# SCH_Roboliga2026_TOP_2026-04-12.net
KiCad netlist of a schematic drawn in EasyEDA
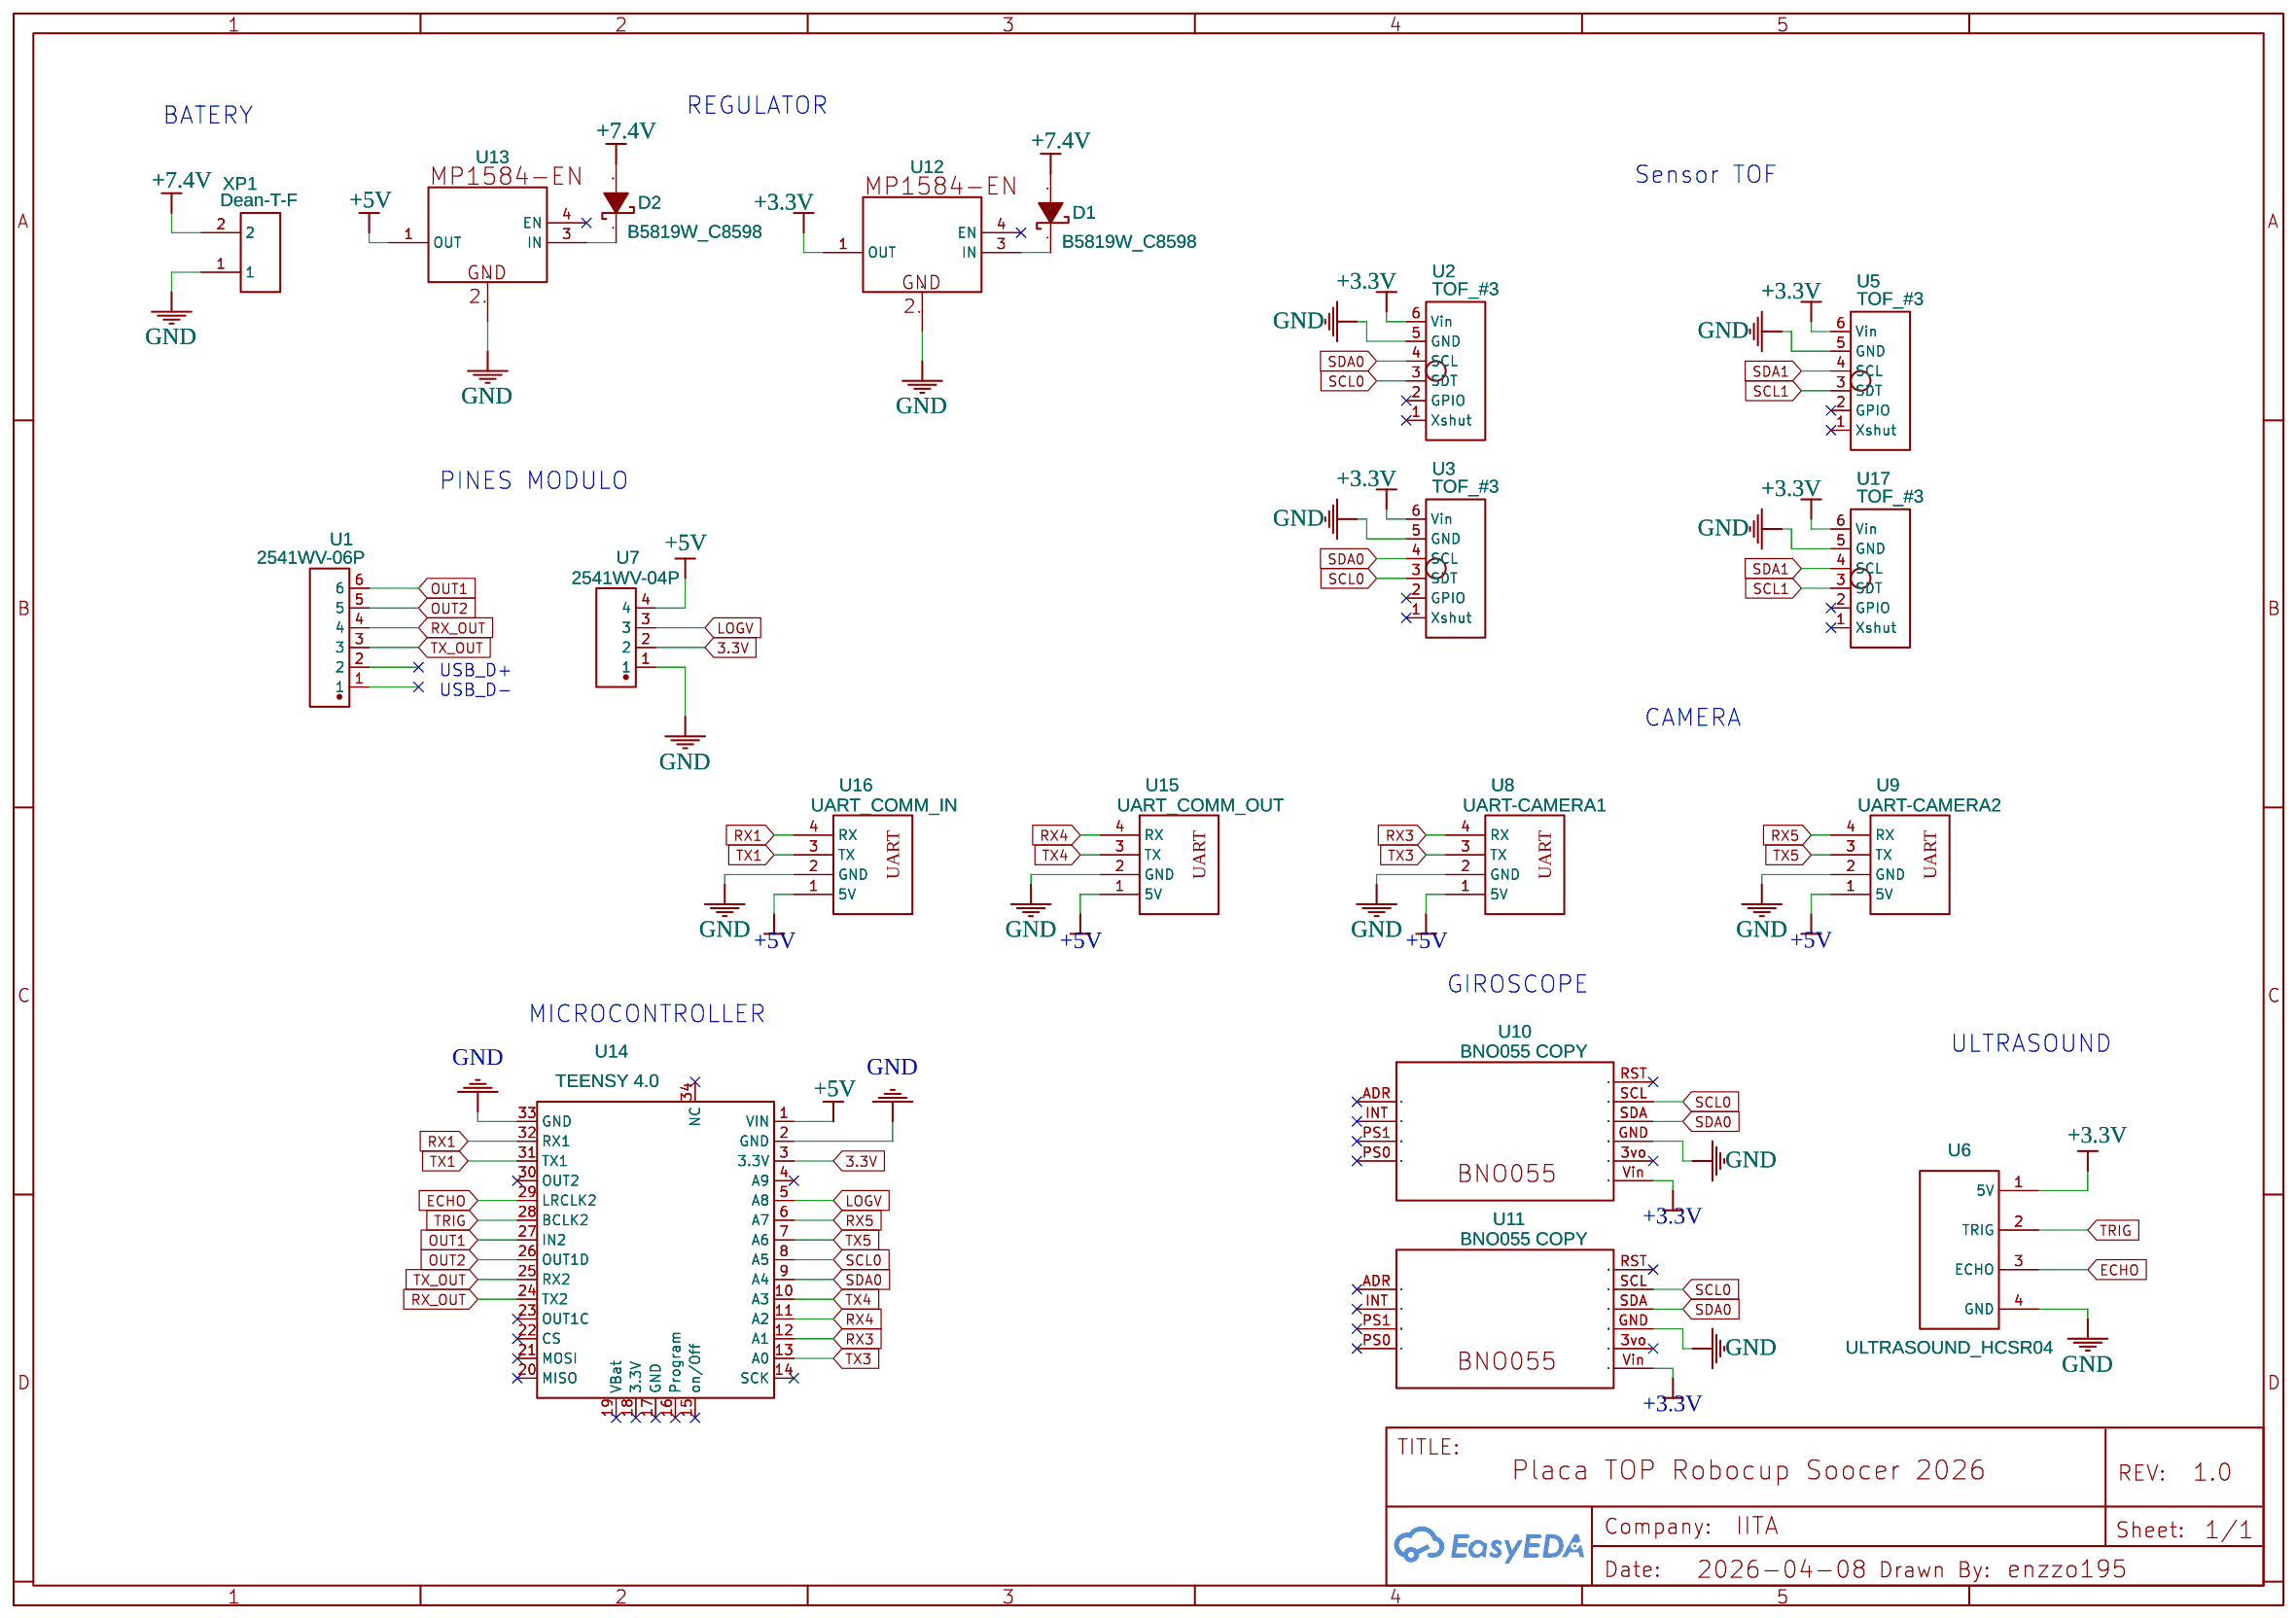
[diagram p0: schematic sheet]

(export (version "E")
  (design (tool "Eeschema 10.0.6"))
  (components
    (comp (ref "D1")
      (value "B5819W_C8598")
      (fields (field (name "Manufacturer Part") "B5819W SL") (field (name "Manufacturer") "CJ(江苏长电/长晶)"))
      (libsource (lib "") (part "B5819W_C8598"))
    )
    (comp (ref "D2")
      (value "B5819W_C8598")
      (fields (field (name "Manufacturer Part") "B5819W SL") (field (name "Manufacturer") "CJ(江苏长电/长晶)"))
      (libsource (lib "") (part "B5819W_C8598"))
    )
    (comp (ref "U1")
      (value "2541WV-06P")
      (fields (field (name "Manufacturer") "HanElectricity(瀚源)"))
      (libsource (lib "") (part "2541WV-06P"))
    )
    (comp (ref "U2") (value "TOF_#3") (libsource (lib "") (part "TOF_#3")))
    (comp (ref "U3") (value "TOF_#3") (libsource (lib "") (part "TOF_#3")))
    (comp (ref "U5") (value "TOF_#3") (libsource (lib "") (part "TOF_#3")))
    (comp (ref "U6") (value "ULTRASOUND_HCSR04") (libsource (lib "") (part "SIMBOLO_HCSR04")))
    (comp (ref "U7")
      (value "2541WV-04P")
      (fields (field (name "Manufacturer") "HanElectricity(瀚源)"))
      (libsource (lib "") (part "2541WV-04P"))
    )
    (comp (ref "U8")
      (value "UART-CAMERA1")
      (fields (field (name "Manufacturer Part") "UART"))
      (libsource (lib "") (part "UART"))
    )
    (comp (ref "U9")
      (value "UART-CAMERA2")
      (fields (field (name "Manufacturer Part") "UART"))
      (libsource (lib "") (part "UART"))
    )
    (comp (ref "U10") (value "BNO055 COPY") (libsource (lib "") (part "BNO055 COPY")))
    (comp (ref "U11") (value "BNO055 COPY") (libsource (lib "") (part "BNO055 COPY")))
    (comp (ref "U12")
      (value "MP1584EN 4-Pin SIP Module")
      (libsource (lib "") (part "MP1584EN 4-Pin SIP Module"))
    )
    (comp (ref "U13")
      (value "MP1584EN 4-Pin SIP Module")
      (libsource (lib "") (part "MP1584EN 4-Pin SIP Module"))
    )
    (comp (ref "U14")
      (value "TEENSY 4.0")
      (fields (field (name "Manufacturer Part") "Teensy 4.0"))
      (libsource (lib "") (part "TEENSY 4.0"))
    )
    (comp (ref "U15")
      (value "UART_COMM_OUT")
      (fields (field (name "Manufacturer Part") "UART"))
      (libsource (lib "") (part "UART"))
    )
    (comp (ref "U16")
      (value "UART_COMM_IN")
      (fields (field (name "Manufacturer Part") "UART"))
      (libsource (lib "") (part "UART"))
    )
    (comp (ref "U17") (value "TOF_#3") (libsource (lib "") (part "TOF_#3")))
    (comp (ref "XP1") (value "Dean-T-F") (libsource (lib "") (part "Dean-T-F")))
  )
  (nets
    (net (code "1") (name "+3.3V") (class "Default")
      (node (ref "U10") (pin "Vin") (pinfunction "Vin_Vin") (pintype "unspecified"))
      (node (ref "U11") (pin "Vin") (pinfunction "Vin_Vin") (pintype "unspecified"))
      (node (ref "U12") (pin "1") (pinfunction "OUT_1") (pintype "unspecified"))
      (node (ref "U17") (pin "6") (pinfunction "Vin_6") (pintype "unspecified"))
      (node (ref "U2") (pin "6") (pinfunction "Vin_6") (pintype "unspecified"))
      (node (ref "U3") (pin "6") (pinfunction "Vin_6") (pintype "unspecified"))
      (node (ref "U5") (pin "6") (pinfunction "Vin_6") (pintype "unspecified"))
      (node (ref "U6") (pin "1") (pinfunction "5V_1") (pintype "unspecified"))
    )
    (net (code "2") (name "+5V") (class "Default")
      (node (ref "U13") (pin "1") (pinfunction "OUT_1") (pintype "unspecified"))
      (node (ref "U14") (pin "1") (pinfunction "VIN_1") (pintype "unspecified"))
      (node (ref "U15") (pin "1") (pinfunction "5V_1") (pintype "unspecified"))
      (node (ref "U16") (pin "1") (pinfunction "5V_1") (pintype "unspecified"))
      (node (ref "U7") (pin "4") (pinfunction "4_4") (pintype "unspecified"))
      (node (ref "U8") (pin "1") (pinfunction "5V_1") (pintype "unspecified"))
      (node (ref "U9") (pin "1") (pinfunction "5V_1") (pintype "unspecified"))
    )
    (net (code "3") (name "+7.4V") (class "Default")
      (node (ref "D1") (pin "2") (pinfunction "+_2") (pintype "unspecified"))
      (node (ref "D2") (pin "2") (pinfunction "+_2") (pintype "unspecified"))
      (node (ref "XP1") (pin "2") (pinfunction "2_2") (pintype "unspecified"))
    )
    (net (code "4") (name "3.3V") (class "Default")
      (node (ref "U14") (pin "3") (pinfunction "3.3V_3") (pintype "unspecified"))
      (node (ref "U7") (pin "2") (pinfunction "2_2") (pintype "unspecified"))
    )
    (net (code "5") (name "ECHO") (class "Default")
      (node (ref "U14") (pin "29") (pinfunction "LRCLK2_29") (pintype "unspecified"))
      (node (ref "U6") (pin "3") (pinfunction "ECHO_3") (pintype "unspecified"))
    )
    (net (code "6") (name "GND") (class "Default")
      (node (ref "U10") (pin "GND") (pinfunction "GND_GND") (pintype "unspecified"))
      (node (ref "U11") (pin "GND") (pinfunction "GND_GND") (pintype "unspecified"))
      (node (ref "U12") (pin "2") (pinfunction "GND_2") (pintype "unspecified"))
      (node (ref "U13") (pin "2") (pinfunction "GND_2") (pintype "unspecified"))
      (node (ref "U14") (pin "2") (pinfunction "GND_2") (pintype "unspecified"))
      (node (ref "U14") (pin "33") (pinfunction "GND_33") (pintype "unspecified"))
      (node (ref "U15") (pin "2") (pinfunction "GND_2") (pintype "unspecified"))
      (node (ref "U16") (pin "2") (pinfunction "GND_2") (pintype "unspecified"))
      (node (ref "U17") (pin "5") (pinfunction "GND_5") (pintype "unspecified"))
      (node (ref "U2") (pin "5") (pinfunction "GND_5") (pintype "unspecified"))
      (node (ref "U3") (pin "5") (pinfunction "GND_5") (pintype "unspecified"))
      (node (ref "U5") (pin "5") (pinfunction "GND_5") (pintype "unspecified"))
      (node (ref "U6") (pin "4") (pinfunction "GND_4") (pintype "unspecified"))
      (node (ref "U7") (pin "1") (pinfunction "1_1") (pintype "unspecified"))
      (node (ref "U8") (pin "2") (pinfunction "GND_2") (pintype "unspecified"))
      (node (ref "U9") (pin "2") (pinfunction "GND_2") (pintype "unspecified"))
      (node (ref "XP1") (pin "1") (pinfunction "1_1") (pintype "unspecified"))
    )
    (net (code "7") (name "LOGV") (class "Default")
      (node (ref "U14") (pin "5") (pinfunction "A8_5") (pintype "unspecified"))
      (node (ref "U7") (pin "3") (pinfunction "3_3") (pintype "unspecified"))
    )
    (net (code "8") (name "Net-(D1--)") (class "Default")
      (node (ref "D1") (pin "1") (pinfunction "-_1") (pintype "unspecified"))
      (node (ref "U12") (pin "3") (pinfunction "IN_3") (pintype "unspecified"))
    )
    (net (code "9") (name "Net-(D2--)") (class "Default")
      (node (ref "D2") (pin "1") (pinfunction "-_1") (pintype "unspecified"))
      (node (ref "U13") (pin "3") (pinfunction "IN_3") (pintype "unspecified"))
    )
    (net (code "10") (name "OUT1") (class "Default")
      (node (ref "U1") (pin "6") (pinfunction "6_6") (pintype "unspecified"))
      (node (ref "U14") (pin "27") (pinfunction "IN2_27") (pintype "unspecified"))
    )
    (net (code "11") (name "OUT2") (class "Default")
      (node (ref "U1") (pin "5") (pinfunction "5_5") (pintype "unspecified"))
      (node (ref "U14") (pin "26") (pinfunction "OUT1D_26") (pintype "unspecified"))
    )
    (net (code "12") (name "RX1") (class "Default")
      (node (ref "U14") (pin "32") (pinfunction "RX1_32") (pintype "unspecified"))
      (node (ref "U16") (pin "4") (pinfunction "RX_4") (pintype "unspecified"))
    )
    (net (code "13") (name "RX3") (class "Default")
      (node (ref "U14") (pin "12") (pinfunction "A1_12") (pintype "unspecified"))
      (node (ref "U8") (pin "4") (pinfunction "RX_4") (pintype "unspecified"))
    )
    (net (code "14") (name "RX4") (class "Default")
      (node (ref "U14") (pin "11") (pinfunction "A2_11") (pintype "unspecified"))
      (node (ref "U15") (pin "4") (pinfunction "RX_4") (pintype "unspecified"))
    )
    (net (code "15") (name "RX5") (class "Default")
      (node (ref "U14") (pin "6") (pinfunction "A7_6") (pintype "unspecified"))
      (node (ref "U9") (pin "4") (pinfunction "RX_4") (pintype "unspecified"))
    )
    (net (code "16") (name "RX_OUT") (class "Default")
      (node (ref "U1") (pin "4") (pinfunction "4_4") (pintype "unspecified"))
      (node (ref "U14") (pin "24") (pinfunction "TX2_24") (pintype "unspecified"))
    )
    (net (code "17") (name "SCL0") (class "Default")
      (node (ref "U10") (pin "SCL") (pinfunction "SCL_SCL") (pintype "unspecified"))
      (node (ref "U11") (pin "SCL") (pinfunction "SCL_SCL") (pintype "unspecified"))
      (node (ref "U14") (pin "8") (pinfunction "A5_8") (pintype "unspecified"))
      (node (ref "U2") (pin "3") (pinfunction "SDT_3") (pintype "unspecified"))
      (node (ref "U3") (pin "3") (pinfunction "SDT_3") (pintype "unspecified"))
    )
    (net (code "18") (name "SCL1") (class "Default")
      (node (ref "U17") (pin "3") (pinfunction "SDT_3") (pintype "unspecified"))
      (node (ref "U5") (pin "3") (pinfunction "SDT_3") (pintype "unspecified"))
    )
    (net (code "19") (name "SDA0") (class "Default")
      (node (ref "U10") (pin "SDA") (pinfunction "SDA_SDA") (pintype "unspecified"))
      (node (ref "U11") (pin "SDA") (pinfunction "SDA_SDA") (pintype "unspecified"))
      (node (ref "U14") (pin "9") (pinfunction "A4_9") (pintype "unspecified"))
      (node (ref "U2") (pin "4") (pinfunction "SCL_4") (pintype "unspecified"))
      (node (ref "U3") (pin "4") (pinfunction "SCL_4") (pintype "unspecified"))
    )
    (net (code "20") (name "SDA1") (class "Default")
      (node (ref "U17") (pin "4") (pinfunction "SCL_4") (pintype "unspecified"))
      (node (ref "U5") (pin "4") (pinfunction "SCL_4") (pintype "unspecified"))
    )
    (net (code "21") (name "TRIG") (class "Default")
      (node (ref "U14") (pin "28") (pinfunction "BCLK2_28") (pintype "unspecified"))
      (node (ref "U6") (pin "2") (pinfunction "TRIG_2") (pintype "unspecified"))
    )
    (net (code "22") (name "TX1") (class "Default")
      (node (ref "U14") (pin "31") (pinfunction "TX1_31") (pintype "unspecified"))
      (node (ref "U16") (pin "3") (pinfunction "TX_3") (pintype "unspecified"))
    )
    (net (code "23") (name "TX3") (class "Default")
      (node (ref "U14") (pin "13") (pinfunction "A0_13") (pintype "unspecified"))
      (node (ref "U8") (pin "3") (pinfunction "TX_3") (pintype "unspecified"))
    )
    (net (code "24") (name "TX4") (class "Default")
      (node (ref "U14") (pin "10") (pinfunction "A3_10") (pintype "unspecified"))
      (node (ref "U15") (pin "3") (pinfunction "TX_3") (pintype "unspecified"))
    )
    (net (code "25") (name "TX5") (class "Default")
      (node (ref "U14") (pin "7") (pinfunction "A6_7") (pintype "unspecified"))
      (node (ref "U9") (pin "3") (pinfunction "TX_3") (pintype "unspecified"))
    )
    (net (code "26") (name "TX_OUT") (class "Default")
      (node (ref "U1") (pin "3") (pinfunction "3_3") (pintype "unspecified"))
      (node (ref "U14") (pin "25") (pinfunction "RX2_25") (pintype "unspecified"))
    )
    (net (code "27") (name "unconnected-(U1-Pad1)") (class "Default")
      (node (ref "U1") (pin "1") (pinfunction "1_1") (pintype "unspecified+no_connect"))
    )
    (net (code "28") (name "unconnected-(U1-Pad2)") (class "Default")
      (node (ref "U1") (pin "2") (pinfunction "2_2") (pintype "unspecified+no_connect"))
    )
    (net (code "29") (name "unconnected-(U2-GPIO-Pad2)") (class "Default")
      (node (ref "U2") (pin "2") (pinfunction "GPIO_2") (pintype "unspecified+no_connect"))
    )
    (net (code "30") (name "unconnected-(U2-Xshut-Pad1)") (class "Default")
      (node (ref "U2") (pin "1") (pinfunction "Xshut_1") (pintype "unspecified+no_connect"))
    )
    (net (code "31") (name "unconnected-(U3-GPIO-Pad2)") (class "Default")
      (node (ref "U3") (pin "2") (pinfunction "GPIO_2") (pintype "unspecified+no_connect"))
    )
    (net (code "32") (name "unconnected-(U3-Xshut-Pad1)") (class "Default")
      (node (ref "U3") (pin "1") (pinfunction "Xshut_1") (pintype "unspecified+no_connect"))
    )
    (net (code "33") (name "unconnected-(U5-GPIO-Pad2)") (class "Default")
      (node (ref "U5") (pin "2") (pinfunction "GPIO_2") (pintype "unspecified+no_connect"))
    )
    (net (code "34") (name "unconnected-(U5-Xshut-Pad1)") (class "Default")
      (node (ref "U5") (pin "1") (pinfunction "Xshut_1") (pintype "unspecified+no_connect"))
    )
    (net (code "35") (name "unconnected-(U10-Pad3vo)") (class "Default")
      (node (ref "U10") (pin "3vo") (pinfunction "3vo_3vo") (pintype "unspecified+no_connect"))
    )
    (net (code "36") (name "unconnected-(U10-PadADR)") (class "Default")
      (node (ref "U10") (pin "ADR") (pinfunction "ADR_ADR") (pintype "unspecified+no_connect"))
    )
    (net (code "37") (name "unconnected-(U10-PadINT)") (class "Default")
      (node (ref "U10") (pin "INT") (pinfunction "INT_INT") (pintype "unspecified+no_connect"))
    )
    (net (code "38") (name "unconnected-(U10-PadPS0)") (class "Default")
      (node (ref "U10") (pin "PS0") (pinfunction "PS0_PS0") (pintype "unspecified+no_connect"))
    )
    (net (code "39") (name "unconnected-(U10-PadPS1)") (class "Default")
      (node (ref "U10") (pin "PS1") (pinfunction "PS1_PS1") (pintype "unspecified+no_connect"))
    )
    (net (code "40") (name "unconnected-(U10-PadRST)") (class "Default")
      (node (ref "U10") (pin "RST") (pinfunction "RST_RST") (pintype "unspecified+no_connect"))
    )
    (net (code "41") (name "unconnected-(U11-Pad3vo)") (class "Default")
      (node (ref "U11") (pin "3vo") (pinfunction "3vo_3vo") (pintype "unspecified+no_connect"))
    )
    (net (code "42") (name "unconnected-(U11-PadADR)") (class "Default")
      (node (ref "U11") (pin "ADR") (pinfunction "ADR_ADR") (pintype "unspecified+no_connect"))
    )
    (net (code "43") (name "unconnected-(U11-PadINT)") (class "Default")
      (node (ref "U11") (pin "INT") (pinfunction "INT_INT") (pintype "unspecified+no_connect"))
    )
    (net (code "44") (name "unconnected-(U11-PadPS0)") (class "Default")
      (node (ref "U11") (pin "PS0") (pinfunction "PS0_PS0") (pintype "unspecified+no_connect"))
    )
    (net (code "45") (name "unconnected-(U11-PadPS1)") (class "Default")
      (node (ref "U11") (pin "PS1") (pinfunction "PS1_PS1") (pintype "unspecified+no_connect"))
    )
    (net (code "46") (name "unconnected-(U11-PadRST)") (class "Default")
      (node (ref "U11") (pin "RST") (pinfunction "RST_RST") (pintype "unspecified+no_connect"))
    )
    (net (code "47") (name "unconnected-(U12-EN-Pad4)") (class "Default")
      (node (ref "U12") (pin "4") (pinfunction "EN_4") (pintype "unspecified+no_connect"))
    )
    (net (code "48") (name "unconnected-(U13-EN-Pad4)") (class "Default")
      (node (ref "U13") (pin "4") (pinfunction "EN_4") (pintype "unspecified+no_connect"))
    )
    (net (code "49") (name "unconnected-(U14-3.3V-Pad18)") (class "Default")
      (node (ref "U14") (pin "18") (pinfunction "3.3V_18") (pintype "unspecified+no_connect"))
    )
    (net (code "50") (name "unconnected-(U14-A9-Pad4)") (class "Default")
      (node (ref "U14") (pin "4") (pinfunction "A9_4") (pintype "unspecified+no_connect"))
    )
    (net (code "51") (name "unconnected-(U14-CS-Pad22)") (class "Default")
      (node (ref "U14") (pin "22") (pinfunction "CS_22") (pintype "unspecified+no_connect"))
    )
    (net (code "52") (name "unconnected-(U14-GND-Pad17)") (class "Default")
      (node (ref "U14") (pin "17") (pinfunction "GND_17") (pintype "unspecified+no_connect"))
    )
    (net (code "53") (name "unconnected-(U14-MISO-Pad20)") (class "Default")
      (node (ref "U14") (pin "20") (pinfunction "MISO_20") (pintype "unspecified+no_connect"))
    )
    (net (code "54") (name "unconnected-(U14-MOSI-Pad21)") (class "Default")
      (node (ref "U14") (pin "21") (pinfunction "MOSI_21") (pintype "unspecified+no_connect"))
    )
    (net (code "55") (name "unconnected-(U14-NC-Pad34)") (class "Default")
      (node (ref "U14") (pin "34") (pinfunction "NC_34") (pintype "unspecified+no_connect"))
    )
    (net (code "56") (name "unconnected-(U14-OUT1C-Pad23)") (class "Default")
      (node (ref "U14") (pin "23") (pinfunction "OUT1C_23") (pintype "unspecified+no_connect"))
    )
    (net (code "57") (name "unconnected-(U14-OUT2-Pad30)") (class "Default")
      (node (ref "U14") (pin "30") (pinfunction "OUT2_30") (pintype "unspecified+no_connect"))
    )
    (net (code "58") (name "unconnected-(U14-Program-Pad16)") (class "Default")
      (node (ref "U14") (pin "16") (pinfunction "Program_16") (pintype "unspecified+no_connect"))
    )
    (net (code "59") (name "unconnected-(U14-SCK-Pad14)") (class "Default")
      (node (ref "U14") (pin "14") (pinfunction "SCK_14") (pintype "unspecified+no_connect"))
    )
    (net (code "60") (name "unconnected-(U14-VBat-Pad19)") (class "Default")
      (node (ref "U14") (pin "19") (pinfunction "VBat_19") (pintype "unspecified+no_connect"))
    )
    (net (code "61") (name "unconnected-(U14-on{slash}Off-Pad15)") (class "Default")
      (node (ref "U14") (pin "15") (pinfunction "on/Off_15") (pintype "unspecified+no_connect"))
    )
    (net (code "62") (name "unconnected-(U17-GPIO-Pad2)") (class "Default")
      (node (ref "U17") (pin "2") (pinfunction "GPIO_2") (pintype "unspecified+no_connect"))
    )
    (net (code "63") (name "unconnected-(U17-Xshut-Pad1)") (class "Default")
      (node (ref "U17") (pin "1") (pinfunction "Xshut_1") (pintype "unspecified+no_connect"))
    )
  )
)
